# AnalogSigCond2.net
KiCad netlist of a schematic drawn in Altium Designer
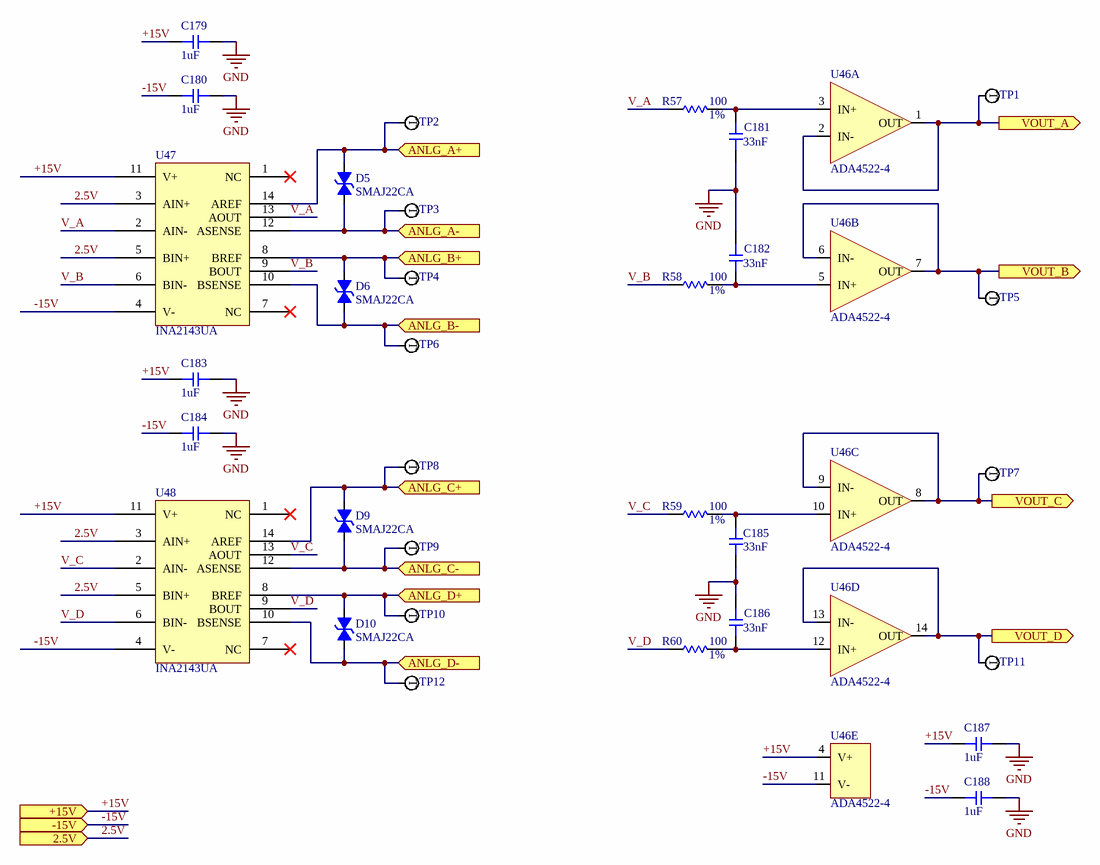
[diagram p0: AnalogSigCond2.SchDoc]

(export (version "E")
  (design (tool "Eeschema 10.0.6"))
  (components
    (comp (ref "C179")
      (value "1uF")
      (footprint "0603-CAP")
      (description "Capacitor")
      (fields
        (field (name "MANUFACTURER") "Samsung")
        (field (name "MANUFACTURER PART NUMBER") "CL10B105MO8NNWC")
      )
      (libsource (lib "AMDC") (part "Capacitor"))
    )
    (comp (ref "C180")
      (value "1uF")
      (footprint "0603-CAP")
      (description "Capacitor")
      (fields
        (field (name "MANUFACTURER") "Samsung")
        (field (name "MANUFACTURER PART NUMBER") "CL10B105MO8NNWC")
      )
      (libsource (lib "AMDC") (part "Capacitor"))
    )
    (comp (ref "C181")
      (value "Capacitor")
      (footprint "0603-CAP")
      (fields
        (field (name "MANUFACTURER") "Kyocera AVX")
        (field (name "MANUFACTURER PART NUMBER") "12065C333KAT2A")
        (field (name "CAPACITANCE") "33nF")
        (field (name "TOLERANCE") "10%")
      )
      (libsource (lib "AMDC") (part "Capacitor"))
    )
    (comp (ref "C182")
      (value "Capacitor")
      (footprint "0603-CAP")
      (fields
        (field (name "MANUFACTURER") "Kyocera AVX")
        (field (name "MANUFACTURER PART NUMBER") "12065C333KAT2A")
        (field (name "CAPACITANCE") "33nF")
        (field (name "TOLERANCE") "10%")
      )
      (libsource (lib "AMDC") (part "Capacitor"))
    )
    (comp (ref "C183")
      (value "1uF")
      (footprint "0603-CAP")
      (description "Capacitor")
      (fields
        (field (name "MANUFACTURER") "Samsung")
        (field (name "MANUFACTURER PART NUMBER") "CL10B105MO8NNWC")
      )
      (libsource (lib "AMDC") (part "Capacitor"))
    )
    (comp (ref "C184")
      (value "1uF")
      (footprint "0603-CAP")
      (description "Capacitor")
      (fields
        (field (name "MANUFACTURER") "Samsung")
        (field (name "MANUFACTURER PART NUMBER") "CL10B105MO8NNWC")
      )
      (libsource (lib "AMDC") (part "Capacitor"))
    )
    (comp (ref "C185")
      (value "Capacitor")
      (footprint "0603-CAP")
      (fields
        (field (name "MANUFACTURER") "Kyocera AVX")
        (field (name "MANUFACTURER PART NUMBER") "12065C333KAT2A")
        (field (name "CAPACITANCE") "33nF")
        (field (name "TOLERANCE") "10%")
      )
      (libsource (lib "AMDC") (part "Capacitor"))
    )
    (comp (ref "C186")
      (value "Capacitor")
      (footprint "0603-CAP")
      (fields
        (field (name "MANUFACTURER") "Kyocera AVX")
        (field (name "MANUFACTURER PART NUMBER") "12065C333KAT2A")
        (field (name "CAPACITANCE") "33nF")
        (field (name "TOLERANCE") "10%")
      )
      (libsource (lib "AMDC") (part "Capacitor"))
    )
    (comp (ref "C187")
      (value "1uF")
      (footprint "0603-CAP")
      (description "Capacitor")
      (fields
        (field (name "MANUFACTURER") "Samsung")
        (field (name "MANUFACTURER PART NUMBER") "CL10B105MO8NNWC")
      )
      (libsource (lib "AMDC") (part "Capacitor"))
    )
    (comp (ref "C188")
      (value "1uF")
      (footprint "0603-CAP")
      (description "Capacitor")
      (fields
        (field (name "MANUFACTURER") "Samsung")
        (field (name "MANUFACTURER PART NUMBER") "CL10B105MO8NNWC")
      )
      (libsource (lib "AMDC") (part "Capacitor"))
    )
    (comp (ref "D5")
      (value "TVS SMAJ22CA")
      (footprint "SMA")
      (description "TVS DIODE 22V 35.5V SMA")
      (fields (field (name "MANUFACTURER") "Bourns") (field (name "MANUFACTURER PART NUMBER") "SMAJ22CA"))
      (libsource (lib "AMDC") (part "TVS SMAJ22CA"))
    )
    (comp (ref "D6")
      (value "TVS SMAJ22CA")
      (footprint "SMA")
      (description "TVS DIODE 22V 35.5V SMA")
      (fields (field (name "MANUFACTURER") "Bourns") (field (name "MANUFACTURER PART NUMBER") "SMAJ22CA"))
      (libsource (lib "AMDC") (part "TVS SMAJ22CA"))
    )
    (comp (ref "D9")
      (value "TVS SMAJ22CA")
      (footprint "SMA")
      (description "TVS DIODE 22V 35.5V SMA")
      (fields (field (name "MANUFACTURER") "Bourns") (field (name "MANUFACTURER PART NUMBER") "SMAJ22CA"))
      (libsource (lib "AMDC") (part "TVS SMAJ22CA"))
    )
    (comp (ref "D10")
      (value "TVS SMAJ22CA")
      (footprint "SMA")
      (description "TVS DIODE 22V 35.5V SMA")
      (fields (field (name "MANUFACTURER") "Bourns") (field (name "MANUFACTURER PART NUMBER") "SMAJ22CA"))
      (libsource (lib "AMDC") (part "TVS SMAJ22CA"))
    )
    (comp (ref "R57")
      (value "Resistor")
      (footprint "0603-RES")
      (fields
        (field (name "MANUFACTURER") "Yageo")
        (field (name "MANUFACTURER PART NUMBER") "AC0603FR-07100RL")
        (field (name "RESISTANCE") "100")
        (field (name "TOLERANCE") "1%")
      )
      (libsource (lib "AMDC") (part "Resistor"))
    )
    (comp (ref "R58")
      (value "Resistor")
      (footprint "0603-RES")
      (fields
        (field (name "MANUFACTURER") "Yageo")
        (field (name "MANUFACTURER PART NUMBER") "AC0603FR-07100RL")
        (field (name "RESISTANCE") "100")
        (field (name "TOLERANCE") "1%")
      )
      (libsource (lib "AMDC") (part "Resistor"))
    )
    (comp (ref "R59")
      (value "Resistor")
      (footprint "0603-RES")
      (fields
        (field (name "MANUFACTURER") "Yageo")
        (field (name "MANUFACTURER PART NUMBER") "AC0603FR-07100RL")
        (field (name "RESISTANCE") "100")
        (field (name "TOLERANCE") "1%")
      )
      (libsource (lib "AMDC") (part "Resistor"))
    )
    (comp (ref "R60")
      (value "Resistor")
      (footprint "0603-RES")
      (fields
        (field (name "MANUFACTURER") "Yageo")
        (field (name "MANUFACTURER PART NUMBER") "AC0603FR-07100RL")
        (field (name "RESISTANCE") "100")
        (field (name "TOLERANCE") "1%")
      )
      (libsource (lib "AMDC") (part "Resistor"))
    )
    (comp (ref "TP1") (value "Test Point") (footprint "RCU-0C") (libsource (lib "AMDC") (part "Test Point")))
    (comp (ref "TP2") (value "Test Point") (footprint "RCU-0C") (libsource (lib "AMDC") (part "Test Point")))
    (comp (ref "TP3") (value "Test Point") (footprint "RCU-0C") (libsource (lib "AMDC") (part "Test Point")))
    (comp (ref "TP4") (value "Test Point") (footprint "RCU-0C") (libsource (lib "AMDC") (part "Test Point")))
    (comp (ref "TP5") (value "Test Point") (footprint "RCU-0C") (libsource (lib "AMDC") (part "Test Point")))
    (comp (ref "TP6") (value "Test Point") (footprint "RCU-0C") (libsource (lib "AMDC") (part "Test Point")))
    (comp (ref "TP7") (value "Test Point") (footprint "RCU-0C") (libsource (lib "AMDC") (part "Test Point")))
    (comp (ref "TP8") (value "Test Point") (footprint "RCU-0C") (libsource (lib "AMDC") (part "Test Point")))
    (comp (ref "TP9") (value "Test Point") (footprint "RCU-0C") (libsource (lib "AMDC") (part "Test Point")))
    (comp (ref "TP10") (value "Test Point") (footprint "RCU-0C") (libsource (lib "AMDC") (part "Test Point")))
    (comp (ref "TP11") (value "Test Point") (footprint "RCU-0C") (libsource (lib "AMDC") (part "Test Point")))
    (comp (ref "TP12") (value "Test Point") (footprint "RCU-0C") (libsource (lib "AMDC") (part "Test Point")))
    (comp (ref "U46")
      (value "ADA4522-4")
      (footprint "TSSOP-14")
      (fields
        (field (name "MANUFACTURER") "Analog Devices")
        (field (name "MANUFACTURER PART NUMBER") "ADA4522-4ARUZ-RL")
      )
      (libsource (lib "AMDC") (part "ADA4522-4"))
    )
    (comp (ref "U47")
      (value "INA2143UA")
      (footprint "SOIC14_N")
      (description "IC OPAMP DIFF 150KHZ 14SOIC")
      (fields (field (name "MANUFACTURER") "Texas Instruments"))
      (libsource (lib "AMDC") (part "INA2143UA"))
    )
    (comp (ref "U48")
      (value "INA2143UA")
      (footprint "SOIC14_N")
      (description "IC OPAMP DIFF 150KHZ 14SOIC")
      (fields (field (name "MANUFACTURER") "Texas Instruments"))
      (libsource (lib "AMDC") (part "INA2143UA"))
    )
  )
  (nets
    (net (code "1") (name "/+15V") (class "Default")
      (node (ref "C179") (pin "1") (pinfunction "1_1") (pintype "passive"))
      (node (ref "C183") (pin "1") (pinfunction "1_1") (pintype "passive"))
      (node (ref "C187") (pin "1") (pinfunction "1_1") (pintype "passive"))
      (node (ref "U46") (pin "4") (pinfunction "V+_4") (pintype "passive"))
      (node (ref "U47") (pin "11") (pinfunction "V+_11") (pintype "passive"))
      (node (ref "U48") (pin "11") (pinfunction "V+_11") (pintype "passive"))
    )
    (net (code "2") (name "/-15V") (class "Default")
      (node (ref "C180") (pin "1") (pinfunction "1_1") (pintype "passive"))
      (node (ref "C184") (pin "1") (pinfunction "1_1") (pintype "passive"))
      (node (ref "C188") (pin "1") (pinfunction "1_1") (pintype "passive"))
      (node (ref "U46") (pin "11") (pinfunction "V-_11") (pintype "passive"))
      (node (ref "U47") (pin "4") (pinfunction "V-_4") (pintype "passive"))
      (node (ref "U48") (pin "4") (pinfunction "V-_4") (pintype "passive"))
    )
    (net (code "3") (name "/2.5V") (class "Default")
      (node (ref "U47") (pin "3") (pinfunction "AIN+_3") (pintype "passive"))
      (node (ref "U47") (pin "5") (pinfunction "BIN+_5") (pintype "passive"))
      (node (ref "U48") (pin "3") (pinfunction "AIN+_3") (pintype "passive"))
      (node (ref "U48") (pin "5") (pinfunction "BIN+_5") (pintype "passive"))
    )
    (net (code "4") (name "/ANLG_A+") (class "Default")
      (node (ref "D5") (pin "2") (pinfunction "2_2") (pintype "passive"))
      (node (ref "TP2") (pin "1") (pinfunction "1_1") (pintype "passive"))
      (node (ref "U47") (pin "14") (pinfunction "AREF_14") (pintype "passive"))
    )
    (net (code "5") (name "/ANLG_A-") (class "Default")
      (node (ref "D5") (pin "1") (pinfunction "1_1") (pintype "passive"))
      (node (ref "TP3") (pin "1") (pinfunction "1_1") (pintype "passive"))
      (node (ref "U47") (pin "12") (pinfunction "ASENSE_12") (pintype "passive"))
    )
    (net (code "6") (name "/ANLG_B+") (class "Default")
      (node (ref "D6") (pin "2") (pinfunction "2_2") (pintype "passive"))
      (node (ref "TP4") (pin "1") (pinfunction "1_1") (pintype "passive"))
      (node (ref "U47") (pin "8") (pinfunction "BREF_8") (pintype "passive"))
    )
    (net (code "7") (name "/ANLG_B-") (class "Default")
      (node (ref "D6") (pin "1") (pinfunction "1_1") (pintype "passive"))
      (node (ref "TP6") (pin "1") (pinfunction "1_1") (pintype "passive"))
      (node (ref "U47") (pin "10") (pinfunction "BSENSE_10") (pintype "passive"))
    )
    (net (code "8") (name "/ANLG_C+") (class "Default")
      (node (ref "D9") (pin "2") (pinfunction "2_2") (pintype "passive"))
      (node (ref "TP8") (pin "1") (pinfunction "1_1") (pintype "passive"))
      (node (ref "U48") (pin "14") (pinfunction "AREF_14") (pintype "passive"))
    )
    (net (code "9") (name "/ANLG_C-") (class "Default")
      (node (ref "D9") (pin "1") (pinfunction "1_1") (pintype "passive"))
      (node (ref "TP9") (pin "1") (pinfunction "1_1") (pintype "passive"))
      (node (ref "U48") (pin "12") (pinfunction "ASENSE_12") (pintype "passive"))
    )
    (net (code "10") (name "/ANLG_D+") (class "Default")
      (node (ref "D10") (pin "2") (pinfunction "2_2") (pintype "passive"))
      (node (ref "TP10") (pin "1") (pinfunction "1_1") (pintype "passive"))
      (node (ref "U48") (pin "8") (pinfunction "BREF_8") (pintype "passive"))
    )
    (net (code "11") (name "/ANLG_D-") (class "Default")
      (node (ref "D10") (pin "1") (pinfunction "1_1") (pintype "passive"))
      (node (ref "TP12") (pin "1") (pinfunction "1_1") (pintype "passive"))
      (node (ref "U48") (pin "10") (pinfunction "BSENSE_10") (pintype "passive"))
    )
    (net (code "12") (name "/VOUT_A") (class "Default")
      (node (ref "TP1") (pin "1") (pinfunction "1_1") (pintype "passive"))
      (node (ref "U46") (pin "1") (pinfunction "OUT_1") (pintype "passive"))
      (node (ref "U46") (pin "2") (pinfunction "IN-_2") (pintype "passive"))
    )
    (net (code "13") (name "/VOUT_B") (class "Default")
      (node (ref "TP5") (pin "1") (pinfunction "1_1") (pintype "passive"))
      (node (ref "U46") (pin "6") (pinfunction "IN-_6") (pintype "passive"))
      (node (ref "U46") (pin "7") (pinfunction "OUT_7") (pintype "passive"))
    )
    (net (code "14") (name "/VOUT_C") (class "Default")
      (node (ref "TP7") (pin "1") (pinfunction "1_1") (pintype "passive"))
      (node (ref "U46") (pin "8") (pinfunction "OUT_8") (pintype "passive"))
      (node (ref "U46") (pin "9") (pinfunction "IN-_9") (pintype "passive"))
    )
    (net (code "15") (name "/VOUT_D") (class "Default")
      (node (ref "TP11") (pin "1") (pinfunction "1_1") (pintype "passive"))
      (node (ref "U46") (pin "13") (pinfunction "IN-_13") (pintype "passive"))
      (node (ref "U46") (pin "14") (pinfunction "OUT_14") (pintype "passive"))
    )
    (net (code "16") (name "/V_A") (class "Default")
      (node (ref "R57") (pin "1") (pinfunction "1_1") (pintype "passive"))
      (node (ref "U47") (pin "13") (pinfunction "AOUT_13") (pintype "passive"))
      (node (ref "U47") (pin "2") (pinfunction "AIN-_2") (pintype "passive"))
    )
    (net (code "17") (name "/V_B") (class "Default")
      (node (ref "R58") (pin "1") (pinfunction "1_1") (pintype "passive"))
      (node (ref "U47") (pin "6") (pinfunction "BIN-_6") (pintype "passive"))
      (node (ref "U47") (pin "9") (pinfunction "BOUT_9") (pintype "passive"))
    )
    (net (code "18") (name "/V_C") (class "Default")
      (node (ref "R59") (pin "1") (pinfunction "1_1") (pintype "passive"))
      (node (ref "U48") (pin "13") (pinfunction "AOUT_13") (pintype "passive"))
      (node (ref "U48") (pin "2") (pinfunction "AIN-_2") (pintype "passive"))
    )
    (net (code "19") (name "/V_D") (class "Default")
      (node (ref "R60") (pin "1") (pinfunction "1_1") (pintype "passive"))
      (node (ref "U48") (pin "6") (pinfunction "BIN-_6") (pintype "passive"))
      (node (ref "U48") (pin "9") (pinfunction "BOUT_9") (pintype "passive"))
    )
    (net (code "20") (name "GND") (class "Default")
      (node (ref "C179") (pin "2") (pinfunction "2_2") (pintype "passive"))
      (node (ref "C180") (pin "2") (pinfunction "2_2") (pintype "passive"))
      (node (ref "C181") (pin "1") (pinfunction "1_1") (pintype "passive"))
      (node (ref "C182") (pin "2") (pinfunction "2_2") (pintype "passive"))
      (node (ref "C183") (pin "2") (pinfunction "2_2") (pintype "passive"))
      (node (ref "C184") (pin "2") (pinfunction "2_2") (pintype "passive"))
      (node (ref "C185") (pin "1") (pinfunction "1_1") (pintype "passive"))
      (node (ref "C186") (pin "2") (pinfunction "2_2") (pintype "passive"))
      (node (ref "C187") (pin "2") (pinfunction "2_2") (pintype "passive"))
      (node (ref "C188") (pin "2") (pinfunction "2_2") (pintype "passive"))
    )
    (net (code "21") (name "Net-(U46A-IN+)") (class "Default")
      (node (ref "C181") (pin "2") (pinfunction "2_2") (pintype "passive"))
      (node (ref "R57") (pin "2") (pinfunction "2_2") (pintype "passive"))
      (node (ref "U46") (pin "3") (pinfunction "IN+_3") (pintype "passive"))
    )
    (net (code "22") (name "Net-(U46B-IN+)") (class "Default")
      (node (ref "C182") (pin "1") (pinfunction "1_1") (pintype "passive"))
      (node (ref "R58") (pin "2") (pinfunction "2_2") (pintype "passive"))
      (node (ref "U46") (pin "5") (pinfunction "IN+_5") (pintype "passive"))
    )
    (net (code "23") (name "Net-(U46C-IN+)") (class "Default")
      (node (ref "C185") (pin "2") (pinfunction "2_2") (pintype "passive"))
      (node (ref "R59") (pin "2") (pinfunction "2_2") (pintype "passive"))
      (node (ref "U46") (pin "10") (pinfunction "IN+_10") (pintype "passive"))
    )
    (net (code "24") (name "Net-(U46D-IN+)") (class "Default")
      (node (ref "C186") (pin "1") (pinfunction "1_1") (pintype "passive"))
      (node (ref "R60") (pin "2") (pinfunction "2_2") (pintype "passive"))
      (node (ref "U46") (pin "12") (pinfunction "IN+_12") (pintype "passive"))
    )
    (net (code "25") (name "unconnected-(U47-NC-Pad1)") (class "Default")
      (node (ref "U47") (pin "1") (pinfunction "NC_1") (pintype "passive+no_connect"))
    )
    (net (code "26") (name "unconnected-(U47-NC-Pad7)") (class "Default")
      (node (ref "U47") (pin "7") (pinfunction "NC_7") (pintype "passive+no_connect"))
    )
    (net (code "27") (name "unconnected-(U48-NC-Pad1)") (class "Default")
      (node (ref "U48") (pin "1") (pinfunction "NC_1") (pintype "passive+no_connect"))
    )
    (net (code "28") (name "unconnected-(U48-NC-Pad7)") (class "Default")
      (node (ref "U48") (pin "7") (pinfunction "NC_7") (pintype "passive+no_connect"))
    )
  )
)
